# MySens-easyESP32b-009.net
KiCad netlist of a schematic drawn in EAGLE
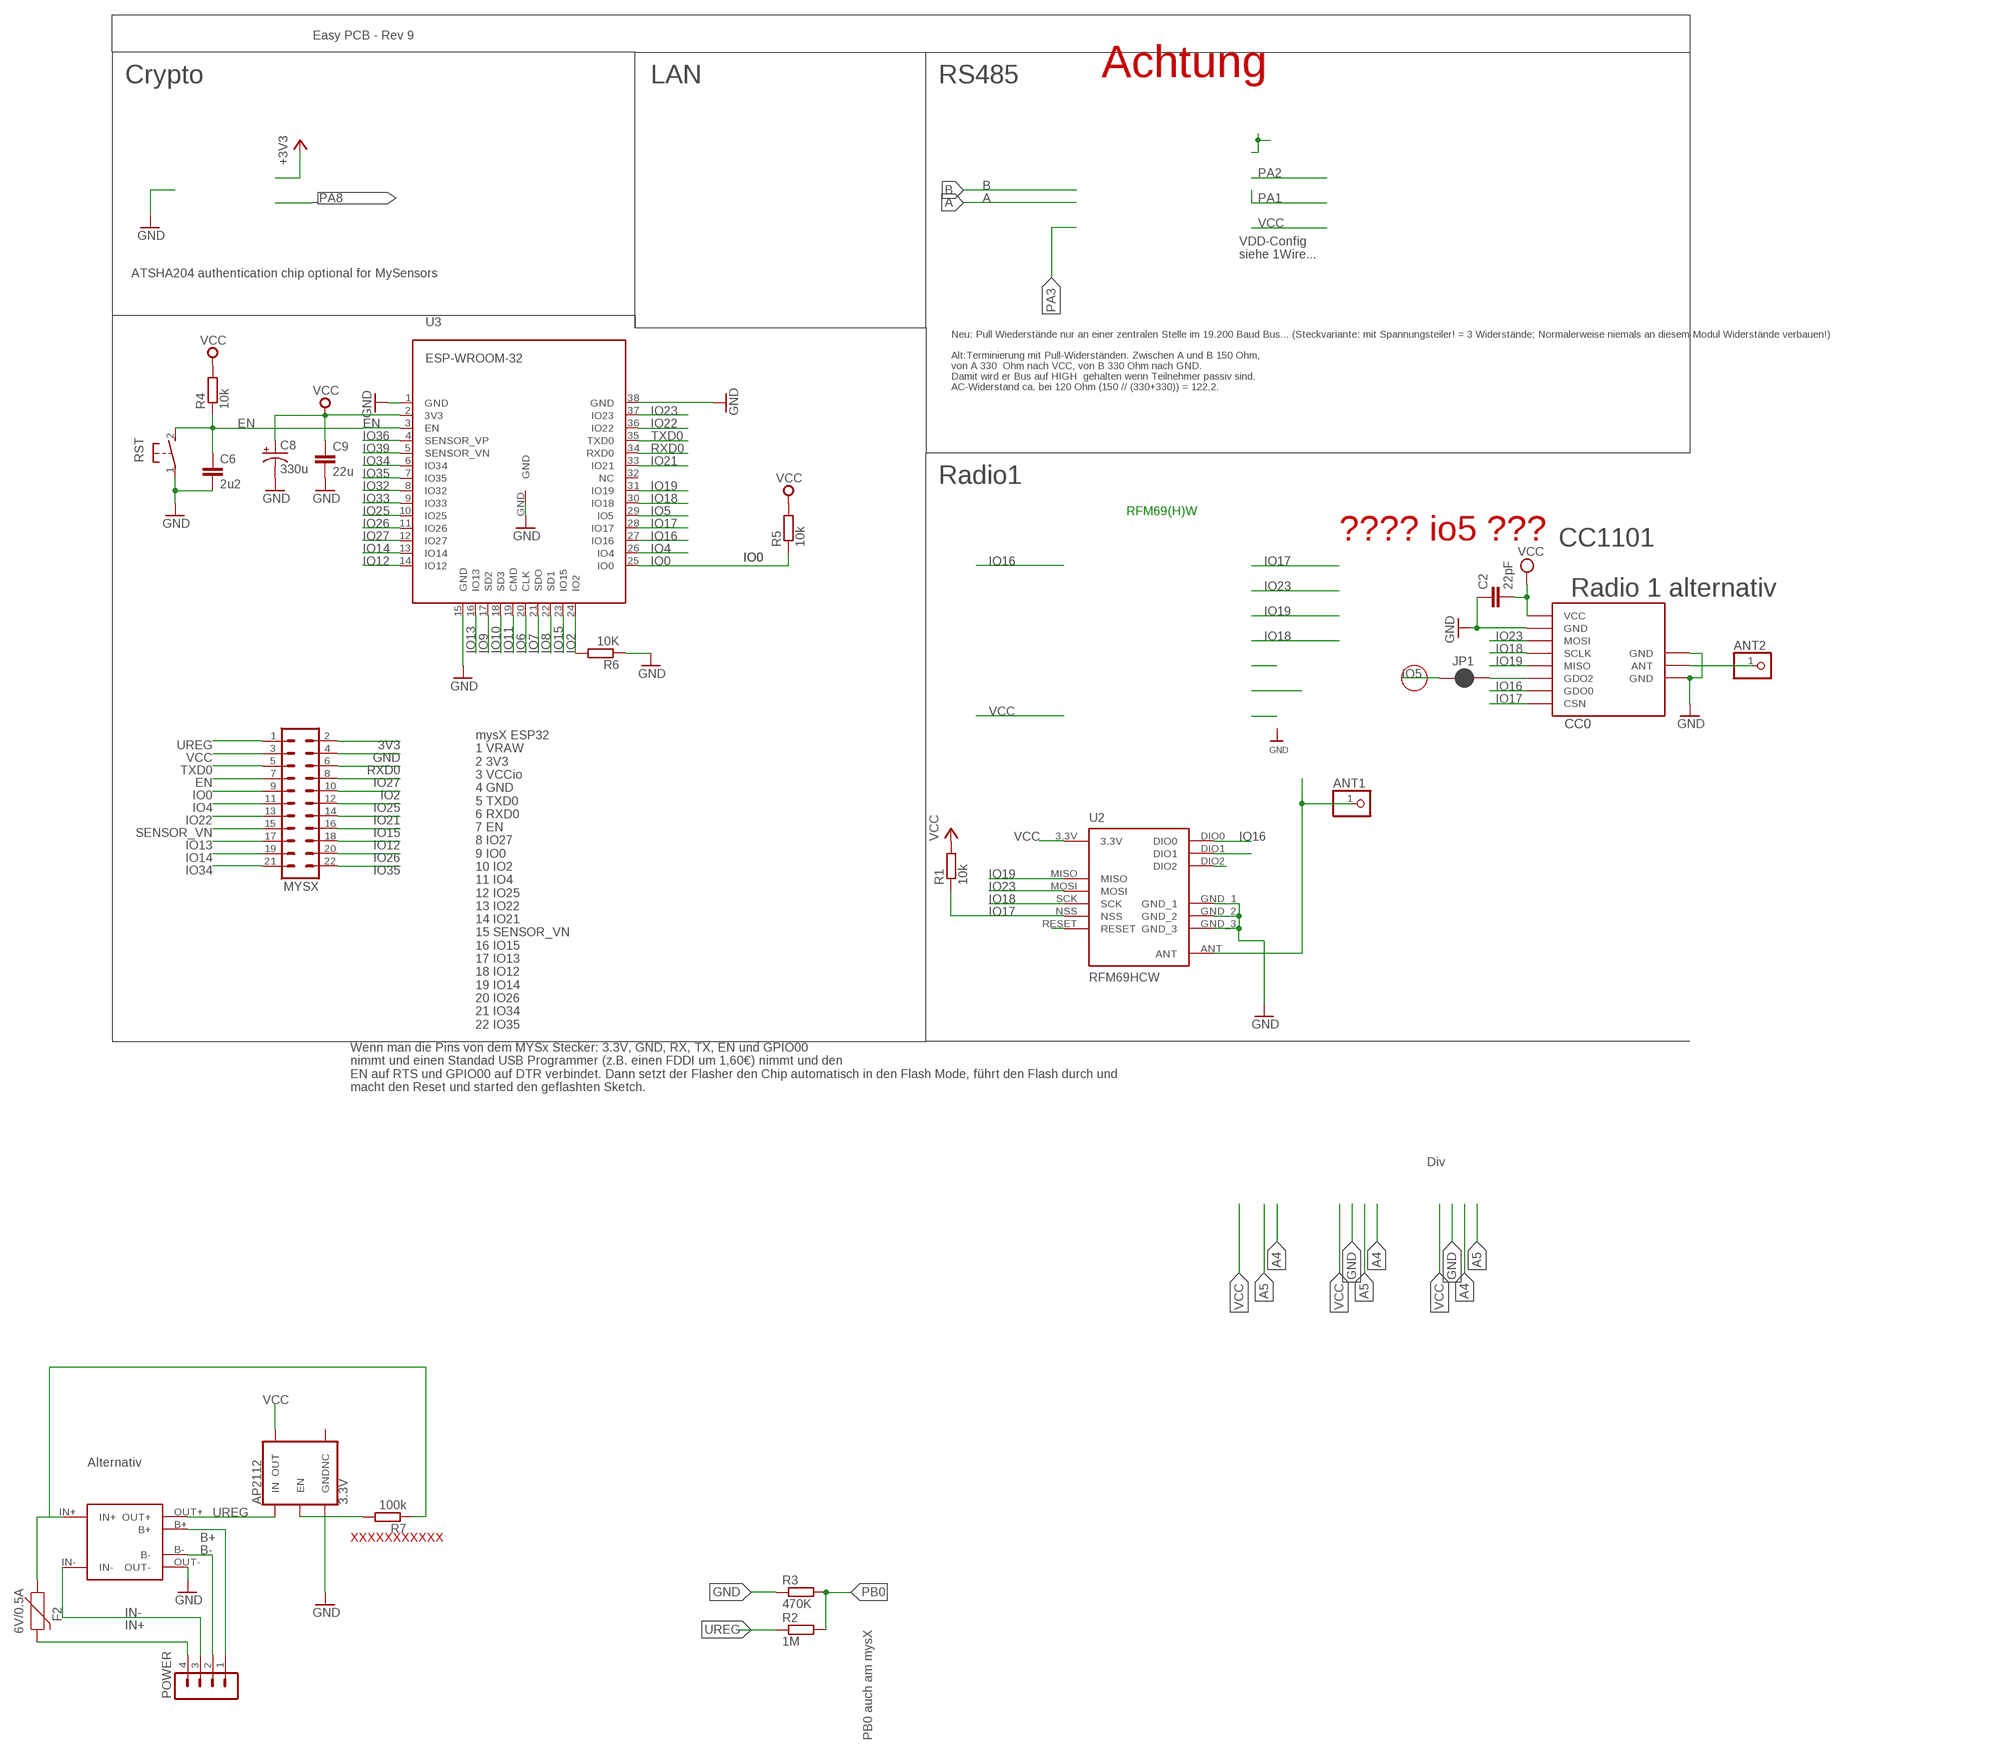
[diagram p0: schematic, sheet 1]

(export (version "E")
  (design (tool "Eeschema 10.0.6"))
  (components
    (comp (ref "ANT1")
      (value "PINHD-1X1")
      (footprint "eagle-import:1X01")
      (libsource (lib "eagle-import") (part "PINHD-1X1"))
    )
    (comp (ref "ANT2")
      (value "PINHD-1X1")
      (footprint "eagle-import:1X01")
      (libsource (lib "eagle-import") (part "PINHD-1X1"))
    )
    (comp (ref "AP2112")
      (value "3.3V")
      (footprint "eagle-import:SOT23-5")
      (libsource (lib "eagle-import") (part "V_REG_AP2112K-3.3V"))
    )
    (comp (ref "C2")
      (value "22pF")
      (footprint "eagle-import:C0805")
      (libsource (lib "eagle-import") (part "C-EUC0805"))
    )
    (comp (ref "C6")
      (value "2u2")
      (footprint "eagle-import:C0805")
      (libsource (lib "eagle-import") (part "rcl@1_C-EUC0805"))
    )
    (comp (ref "C8")
      (value "330u")
      (footprint "eagle-import:VISHAY_C")
      (libsource (lib "eagle-import") (part "CAP_POLSMD"))
    )
    (comp (ref "C9")
      (value "22u")
      (footprint "eagle-import:C0805")
      (libsource (lib "eagle-import") (part "rcl@1_C-EUC0805"))
    )
    (comp (ref "CC0")
      (value "CC1101")
      (footprint "eagle-import:CC1101_MODULE1_SMD")
      (libsource (lib "eagle-import") (part "CC1101_MODULE1SMD"))
    )
    (comp (ref "F2")
      (value "6V/0.5A")
      (footprint "eagle-import:1206")
      (libsource (lib "eagle-import") (part "PPTC_HALF-AMP"))
    )
    (comp (ref "JP1")
      (value "JUMPER-SMT_2_NC_PASTE_NO-SILK")
      (footprint "eagle-import:SMT-JUMPER_2_NC_PASTE_NO-SILK")
      (libsource (lib "eagle-import") (part "JUMPER-SMT_2_NC_PASTE_NO-SILK"))
    )
    (comp (ref "MYSX")
      (value "MA11-2")
      (footprint "eagle-import:MA11-2")
      (libsource (lib "eagle-import") (part "MA11-2"))
    )
    (comp (ref "POWER")
      (value "MA04-1")
      (footprint "eagle-import:MA04-1")
      (libsource (lib "eagle-import") (part "MA04-1"))
    )
    (comp (ref "R1")
      (value "10k")
      (footprint "eagle-import:M0805")
      (libsource (lib "eagle-import") (part "R-EU_M0805"))
    )
    (comp (ref "R2")
      (value "1M")
      (footprint "eagle-import:M0805")
      (libsource (lib "eagle-import") (part "R-EU_M0805"))
    )
    (comp (ref "R3")
      (value "470K")
      (footprint "eagle-import:M0805")
      (libsource (lib "eagle-import") (part "R-EU_M0805"))
    )
    (comp (ref "R4")
      (value "10k")
      (footprint "eagle-import:M0805")
      (libsource (lib "eagle-import") (part "rcl@1_R-EU_M0805"))
    )
    (comp (ref "R5")
      (value "10k")
      (footprint "eagle-import:R0603")
      (libsource (lib "eagle-import") (part "R-EU_R0603"))
    )
    (comp (ref "R6")
      (value "10K")
      (footprint "eagle-import:M0805")
      (libsource (lib "eagle-import") (part "R-EU_M0805"))
    )
    (comp (ref "R7")
      (value "100k")
      (footprint "eagle-import:M0805")
      (libsource (lib "eagle-import") (part "R-EU_M0805"))
    )
    (comp (ref "RST")
      (value "DTSM-3")
      (footprint "eagle-import:DTSM-3")
      (libsource (lib "eagle-import") (part "DTSM-3"))
    )
    (comp (ref "TP4056")
      (value "TP4056-MODULE")
      (footprint "eagle-import:TP4056-LITHIUM-PROTECTED-MODULE")
      (libsource (lib "eagle-import") (part "TP4056-MODULE"))
    )
    (comp (ref "U2")
      (value "RFM69HCW")
      (footprint "eagle-import:RFM69HCW-XXXS2")
      (libsource (lib "eagle-import") (part "RFM69HCW"))
    )
    (comp (ref "U3")
      (value "ESP-WROOM-32")
      (footprint "eagle-import:ESP-WROOM-32")
      (libsource (lib "eagle-import") (part "ESP-WROOM-32"))
    )
  )
  (nets
    (net (code "2") (name "/3V3") (class "Default")
      (node (ref "MYSX") (pin "2") (pinfunction "2_2") (pintype "passive"))
    )
    (net (code "3") (name "/B+") (class "Default")
      (node (ref "POWER") (pin "1") (pinfunction "1_1") (pintype "passive"))
      (node (ref "TP4056") (pin "B+") (pinfunction "B+_B+") (pintype "power_in"))
    )
    (net (code "4") (name "/B-") (class "Default")
      (node (ref "POWER") (pin "2") (pinfunction "2_2") (pintype "passive"))
      (node (ref "TP4056") (pin "B-") (pinfunction "B-_B-") (pintype "power_in"))
    )
    (net (code "5") (name "/EN") (class "Default")
      (node (ref "C6") (pin "1") (pinfunction "1_1") (pintype "passive"))
      (node (ref "MYSX") (pin "7") (pinfunction "7_7") (pintype "passive"))
      (node (ref "R4") (pin "1") (pinfunction "1_1") (pintype "passive"))
      (node (ref "RST") (pin "2") (pinfunction "2_2") (pintype "passive"))
      (node (ref "U3") (pin "3") (pinfunction "EN_3") (pintype "bidirectional"))
    )
    (net (code "6") (name "/IN+") (class "Default")
      (node (ref "F2") (pin "2") (pinfunction "2_2") (pintype "bidirectional"))
      (node (ref "POWER") (pin "4") (pinfunction "4_4") (pintype "passive"))
    )
    (net (code "7") (name "/IN-") (class "Default")
      (node (ref "POWER") (pin "3") (pinfunction "3_3") (pintype "passive"))
      (node (ref "TP4056") (pin "IN-") (pinfunction "IN-_IN-") (pintype "power_in"))
    )
    (net (code "8") (name "/IO0") (class "Default")
      (node (ref "MYSX") (pin "9") (pinfunction "9_9") (pintype "passive"))
      (node (ref "R5") (pin "1") (pinfunction "1_1") (pintype "passive"))
      (node (ref "U3") (pin "25") (pinfunction "IO0_25") (pintype "bidirectional"))
    )
    (net (code "9") (name "/IO2") (class "Default")
      (node (ref "MYSX") (pin "10") (pinfunction "10_10") (pintype "passive"))
      (node (ref "R6") (pin "2") (pinfunction "2_2") (pintype "passive"))
      (node (ref "U3") (pin "24") (pinfunction "IO2_24") (pintype "bidirectional"))
    )
    (net (code "10") (name "/IO4") (class "Default")
      (node (ref "MYSX") (pin "11") (pinfunction "11_11") (pintype "passive"))
      (node (ref "U3") (pin "26") (pinfunction "IO4_26") (pintype "bidirectional"))
    )
    (net (code "11") (name "/IO5") (class "Default")
      (node (ref "JP1") (pin "1") (pinfunction "1_1") (pintype "passive"))
      (node (ref "U3") (pin "29") (pinfunction "IO5_29") (pintype "bidirectional"))
    )
    (net (code "12") (name "/IO6") (class "Default")
      (node (ref "U3") (pin "20") (pinfunction "CLK_20") (pintype "bidirectional"))
    )
    (net (code "13") (name "/IO7") (class "Default")
      (node (ref "U3") (pin "21") (pinfunction "SDO_21") (pintype "bidirectional"))
    )
    (net (code "14") (name "/IO8") (class "Default")
      (node (ref "U3") (pin "22") (pinfunction "SD1_22") (pintype "bidirectional"))
    )
    (net (code "15") (name "/IO9") (class "Default")
      (node (ref "U3") (pin "17") (pinfunction "SD2_17") (pintype "bidirectional"))
    )
    (net (code "16") (name "/IO10") (class "Default")
      (node (ref "U3") (pin "18") (pinfunction "SD3_18") (pintype "bidirectional"))
    )
    (net (code "17") (name "/IO11") (class "Default")
      (node (ref "U3") (pin "19") (pinfunction "CMD_19") (pintype "bidirectional"))
    )
    (net (code "18") (name "/IO12") (class "Default")
      (node (ref "MYSX") (pin "18") (pinfunction "18_18") (pintype "passive"))
      (node (ref "U3") (pin "14") (pinfunction "IO12_14") (pintype "bidirectional"))
    )
    (net (code "19") (name "/IO13") (class "Default")
      (node (ref "MYSX") (pin "17") (pinfunction "17_17") (pintype "passive"))
      (node (ref "U3") (pin "16") (pinfunction "IO13_16") (pintype "bidirectional"))
    )
    (net (code "20") (name "/IO14") (class "Default")
      (node (ref "MYSX") (pin "19") (pinfunction "19_19") (pintype "passive"))
      (node (ref "U3") (pin "13") (pinfunction "IO14_13") (pintype "bidirectional"))
    )
    (net (code "21") (name "/IO15") (class "Default")
      (node (ref "MYSX") (pin "16") (pinfunction "16_16") (pintype "passive"))
      (node (ref "U3") (pin "23") (pinfunction "IO15_23") (pintype "bidirectional"))
    )
    (net (code "22") (name "/IO16") (class "Default")
      (node (ref "CC0") (pin "GDO0") (pinfunction "GDO0_GDO0") (pintype "bidirectional"))
      (node (ref "U2") (pin "DIO0") (pinfunction "DIO0_DIO0") (pintype "bidirectional"))
      (node (ref "U3") (pin "27") (pinfunction "IO16_27") (pintype "bidirectional"))
    )
    (net (code "23") (name "/IO17") (class "Default")
      (node (ref "CC0") (pin "CSN") (pinfunction "CSN_CSN") (pintype "bidirectional"))
      (node (ref "R1") (pin "1") (pinfunction "1_1") (pintype "passive"))
      (node (ref "U2") (pin "NSS") (pinfunction "NSS_NSS") (pintype "input"))
      (node (ref "U3") (pin "28") (pinfunction "IO17_28") (pintype "bidirectional"))
    )
    (net (code "24") (name "/IO18") (class "Default")
      (node (ref "CC0") (pin "SCLK") (pinfunction "SCLK_SCLK") (pintype "bidirectional"))
      (node (ref "U2") (pin "SCK") (pinfunction "SCK_SCK") (pintype "input"))
      (node (ref "U3") (pin "30") (pinfunction "IO18_30") (pintype "bidirectional"))
    )
    (net (code "25") (name "/IO19") (class "Default")
      (node (ref "CC0") (pin "MISO") (pinfunction "MISO_MISO") (pintype "bidirectional"))
      (node (ref "U2") (pin "MISO") (pinfunction "MISO_MISO") (pintype "bidirectional"))
      (node (ref "U3") (pin "31") (pinfunction "IO19_31") (pintype "bidirectional"))
    )
    (net (code "26") (name "/IO21") (class "Default")
      (node (ref "MYSX") (pin "14") (pinfunction "14_14") (pintype "passive"))
      (node (ref "U3") (pin "33") (pinfunction "IO21_33") (pintype "bidirectional"))
    )
    (net (code "27") (name "/IO22") (class "Default")
      (node (ref "MYSX") (pin "13") (pinfunction "13_13") (pintype "passive"))
      (node (ref "U3") (pin "36") (pinfunction "IO22_36") (pintype "bidirectional"))
    )
    (net (code "28") (name "/IO23") (class "Default")
      (node (ref "CC0") (pin "MOSI") (pinfunction "MOSI_MOSI") (pintype "bidirectional"))
      (node (ref "U2") (pin "MOSI") (pinfunction "MOSI_MOSI") (pintype "input"))
      (node (ref "U3") (pin "37") (pinfunction "IO23_37") (pintype "bidirectional"))
    )
    (net (code "29") (name "/IO25") (class "Default")
      (node (ref "MYSX") (pin "12") (pinfunction "12_12") (pintype "passive"))
      (node (ref "U3") (pin "10") (pinfunction "IO25_10") (pintype "bidirectional"))
    )
    (net (code "30") (name "/IO26") (class "Default")
      (node (ref "MYSX") (pin "20") (pinfunction "20_20") (pintype "passive"))
      (node (ref "U3") (pin "11") (pinfunction "IO26_11") (pintype "bidirectional"))
    )
    (net (code "31") (name "/IO27") (class "Default")
      (node (ref "MYSX") (pin "8") (pinfunction "8_8") (pintype "passive"))
      (node (ref "U3") (pin "12") (pinfunction "IO27_12") (pintype "bidirectional"))
    )
    (net (code "32") (name "/IO32") (class "Default")
      (node (ref "U3") (pin "8") (pinfunction "IO32_8") (pintype "bidirectional"))
    )
    (net (code "33") (name "/IO33") (class "Default")
      (node (ref "U3") (pin "9") (pinfunction "IO33_9") (pintype "bidirectional"))
    )
    (net (code "34") (name "/IO34") (class "Default")
      (node (ref "MYSX") (pin "21") (pinfunction "21_21") (pintype "passive"))
      (node (ref "U3") (pin "6") (pinfunction "IO34_6") (pintype "bidirectional"))
    )
    (net (code "35") (name "/IO35") (class "Default")
      (node (ref "MYSX") (pin "22") (pinfunction "22_22") (pintype "passive"))
      (node (ref "U3") (pin "7") (pinfunction "IO35_7") (pintype "bidirectional"))
    )
    (net (code "36") (name "/IO36") (class "Default")
      (node (ref "U3") (pin "4") (pinfunction "SENSOR_VP_4") (pintype "bidirectional"))
    )
    (net (code "37") (name "/IO39") (class "Default")
      (node (ref "U3") (pin "5") (pinfunction "SENSOR_VN_5") (pintype "bidirectional"))
    )
    (net (code "41") (name "/RXD0") (class "Default")
      (node (ref "MYSX") (pin "6") (pinfunction "6_6") (pintype "passive"))
      (node (ref "U3") (pin "34") (pinfunction "RXD0_34") (pintype "bidirectional"))
    )
    (net (code "42") (name "/SENSOR_VN") (class "Default")
      (node (ref "MYSX") (pin "15") (pinfunction "15_15") (pintype "passive"))
    )
    (net (code "43") (name "/TXD0") (class "Default")
      (node (ref "MYSX") (pin "5") (pinfunction "5_5") (pintype "passive"))
      (node (ref "U3") (pin "35") (pinfunction "TXD0_35") (pintype "bidirectional"))
    )
    (net (code "48") (name "GND") (class "Default")
      (node (ref "AP2112") (pin "2") (pinfunction "GND_2") (pintype "input"))
      (node (ref "C2") (pin "1") (pinfunction "1_1") (pintype "passive"))
      (node (ref "C6") (pin "2") (pinfunction "2_2") (pintype "passive"))
      (node (ref "C8") (pin "-") (pinfunction "-_-") (pintype "passive"))
      (node (ref "C9") (pin "2") (pinfunction "2_2") (pintype "passive"))
      (node (ref "CC0") (pin "GND@0") (pinfunction "GND_GND@0") (pintype "power_in"))
      (node (ref "CC0") (pin "GND@1") (pinfunction "GND_GND@1") (pintype "power_in"))
      (node (ref "CC0") (pin "GND@2") (pinfunction "GND_GND@2") (pintype "power_in"))
      (node (ref "MYSX") (pin "4") (pinfunction "4_4") (pintype "passive"))
      (node (ref "R3") (pin "1") (pinfunction "1_1") (pintype "passive"))
      (node (ref "R6") (pin "1") (pinfunction "1_1") (pintype "passive"))
      (node (ref "RST") (pin "1") (pinfunction "1_1") (pintype "passive"))
      (node (ref "TP4056") (pin "OUT-") (pinfunction "OUT-_OUT-") (pintype "power_in"))
      (node (ref "U2") (pin "GND_1") (pinfunction "GND_1_GND_1") (pintype "power_in"))
      (node (ref "U2") (pin "GND_2") (pinfunction "GND_2_GND_2") (pintype "power_in"))
      (node (ref "U2") (pin "GND_3") (pinfunction "GND_3_GND_3") (pintype "power_in"))
      (node (ref "U3") (pin "1") (pinfunction "GND_1") (pintype "bidirectional"))
      (node (ref "U3") (pin "15") (pinfunction "GND_15") (pintype "bidirectional"))
      (node (ref "U3") (pin "38") (pinfunction "GND_38") (pintype "bidirectional"))
      (node (ref "U3") (pin "GND") (pinfunction "GND_GND") (pintype "bidirectional"))
    )
    (net (code "49") (name "Net-(ANT1-Pad1)") (class "Default")
      (node (ref "ANT1") (pin "1") (pinfunction "1_1") (pintype "passive"))
      (node (ref "U2") (pin "ANT") (pinfunction "ANT_ANT") (pintype "passive"))
    )
    (net (code "50") (name "Net-(ANT2-Pad1)") (class "Default")
      (node (ref "ANT2") (pin "1") (pinfunction "1_1") (pintype "passive"))
      (node (ref "CC0") (pin "ANT") (pinfunction "ANT_ANT") (pintype "output"))
    )
    (net (code "51") (name "Net-(AP2112-EN)") (class "Default")
      (node (ref "AP2112") (pin "3") (pinfunction "EN_3") (pintype "input"))
      (node (ref "R7") (pin "2") (pinfunction "2_2") (pintype "passive"))
    )
    (net (code "52") (name "Net-(CC0-PadGDO2)") (class "Default")
      (node (ref "CC0") (pin "GDO2") (pinfunction "GDO2_GDO2") (pintype "bidirectional"))
      (node (ref "JP1") (pin "2") (pinfunction "2_2") (pintype "passive"))
    )
    (net (code "53") (name "Net-(F2-Pad1)") (class "Default")
      (node (ref "F2") (pin "1") (pinfunction "1_1") (pintype "bidirectional"))
      (node (ref "R7") (pin "1") (pinfunction "1_1") (pintype "passive"))
      (node (ref "TP4056") (pin "IN+") (pinfunction "IN+_IN+") (pintype "power_in"))
    )
    (net (code "55") (name "PB0") (class "Default")
      (node (ref "R2") (pin "2") (pinfunction "2_2") (pintype "passive"))
      (node (ref "R3") (pin "2") (pinfunction "2_2") (pintype "passive"))
    )
    (net (code "56") (name "UREG") (class "Default")
      (node (ref "AP2112") (pin "1") (pinfunction "IN_1") (pintype "input"))
      (node (ref "MYSX") (pin "1") (pinfunction "1_1") (pintype "passive"))
      (node (ref "R2") (pin "1") (pinfunction "1_1") (pintype "passive"))
      (node (ref "TP4056") (pin "OUT+") (pinfunction "OUT+_OUT+") (pintype "power_in"))
    )
    (net (code "57") (name "VCC") (class "Default")
      (node (ref "AP2112") (pin "5") (pinfunction "OUT_5") (pintype "passive"))
      (node (ref "C2") (pin "2") (pinfunction "2_2") (pintype "passive"))
      (node (ref "C8") (pin "+") (pinfunction "+_+") (pintype "passive"))
      (node (ref "C9") (pin "1") (pinfunction "1_1") (pintype "passive"))
      (node (ref "CC0") (pin "VCC") (pinfunction "VCC_VCC") (pintype "power_in"))
      (node (ref "MYSX") (pin "3") (pinfunction "3_3") (pintype "passive"))
      (node (ref "R1") (pin "2") (pinfunction "2_2") (pintype "passive"))
      (node (ref "R4") (pin "2") (pinfunction "2_2") (pintype "passive"))
      (node (ref "R5") (pin "2") (pinfunction "2_2") (pintype "passive"))
      (node (ref "U2") (pin "3.3V") (pinfunction "3.3V_3.3V") (pintype "power_in"))
      (node (ref "U3") (pin "2") (pinfunction "3V3_2") (pintype "bidirectional"))
    )
    (net (code "58") (name "unconnected-(AP2112-NC-Pad4)") (class "Default")
      (node (ref "AP2112") (pin "4") (pinfunction "NC_4") (pintype "no_connect"))
    )
    (net (code "59") (name "unconnected-(U2-PadDIO1)") (class "Default")
      (node (ref "U2") (pin "DIO1") (pinfunction "DIO1_DIO1") (pintype "bidirectional"))
    )
    (net (code "60") (name "unconnected-(U2-PadDIO2)") (class "Default")
      (node (ref "U2") (pin "DIO2") (pinfunction "DIO2_DIO2") (pintype "bidirectional"))
    )
    (net (code "61") (name "unconnected-(U2-PadRESET)") (class "Default")
      (node (ref "U2") (pin "RESET") (pinfunction "RESET_RESET") (pintype "input"))
    )
    (net (code "62") (name "unconnected-(U3-NC-Pad32)") (class "Default")
      (node (ref "U3") (pin "32") (pinfunction "NC_32") (pintype "bidirectional"))
    )
  )
)
